# BSK3.net
KiCad netlist of a schematic drawn in EAGLE
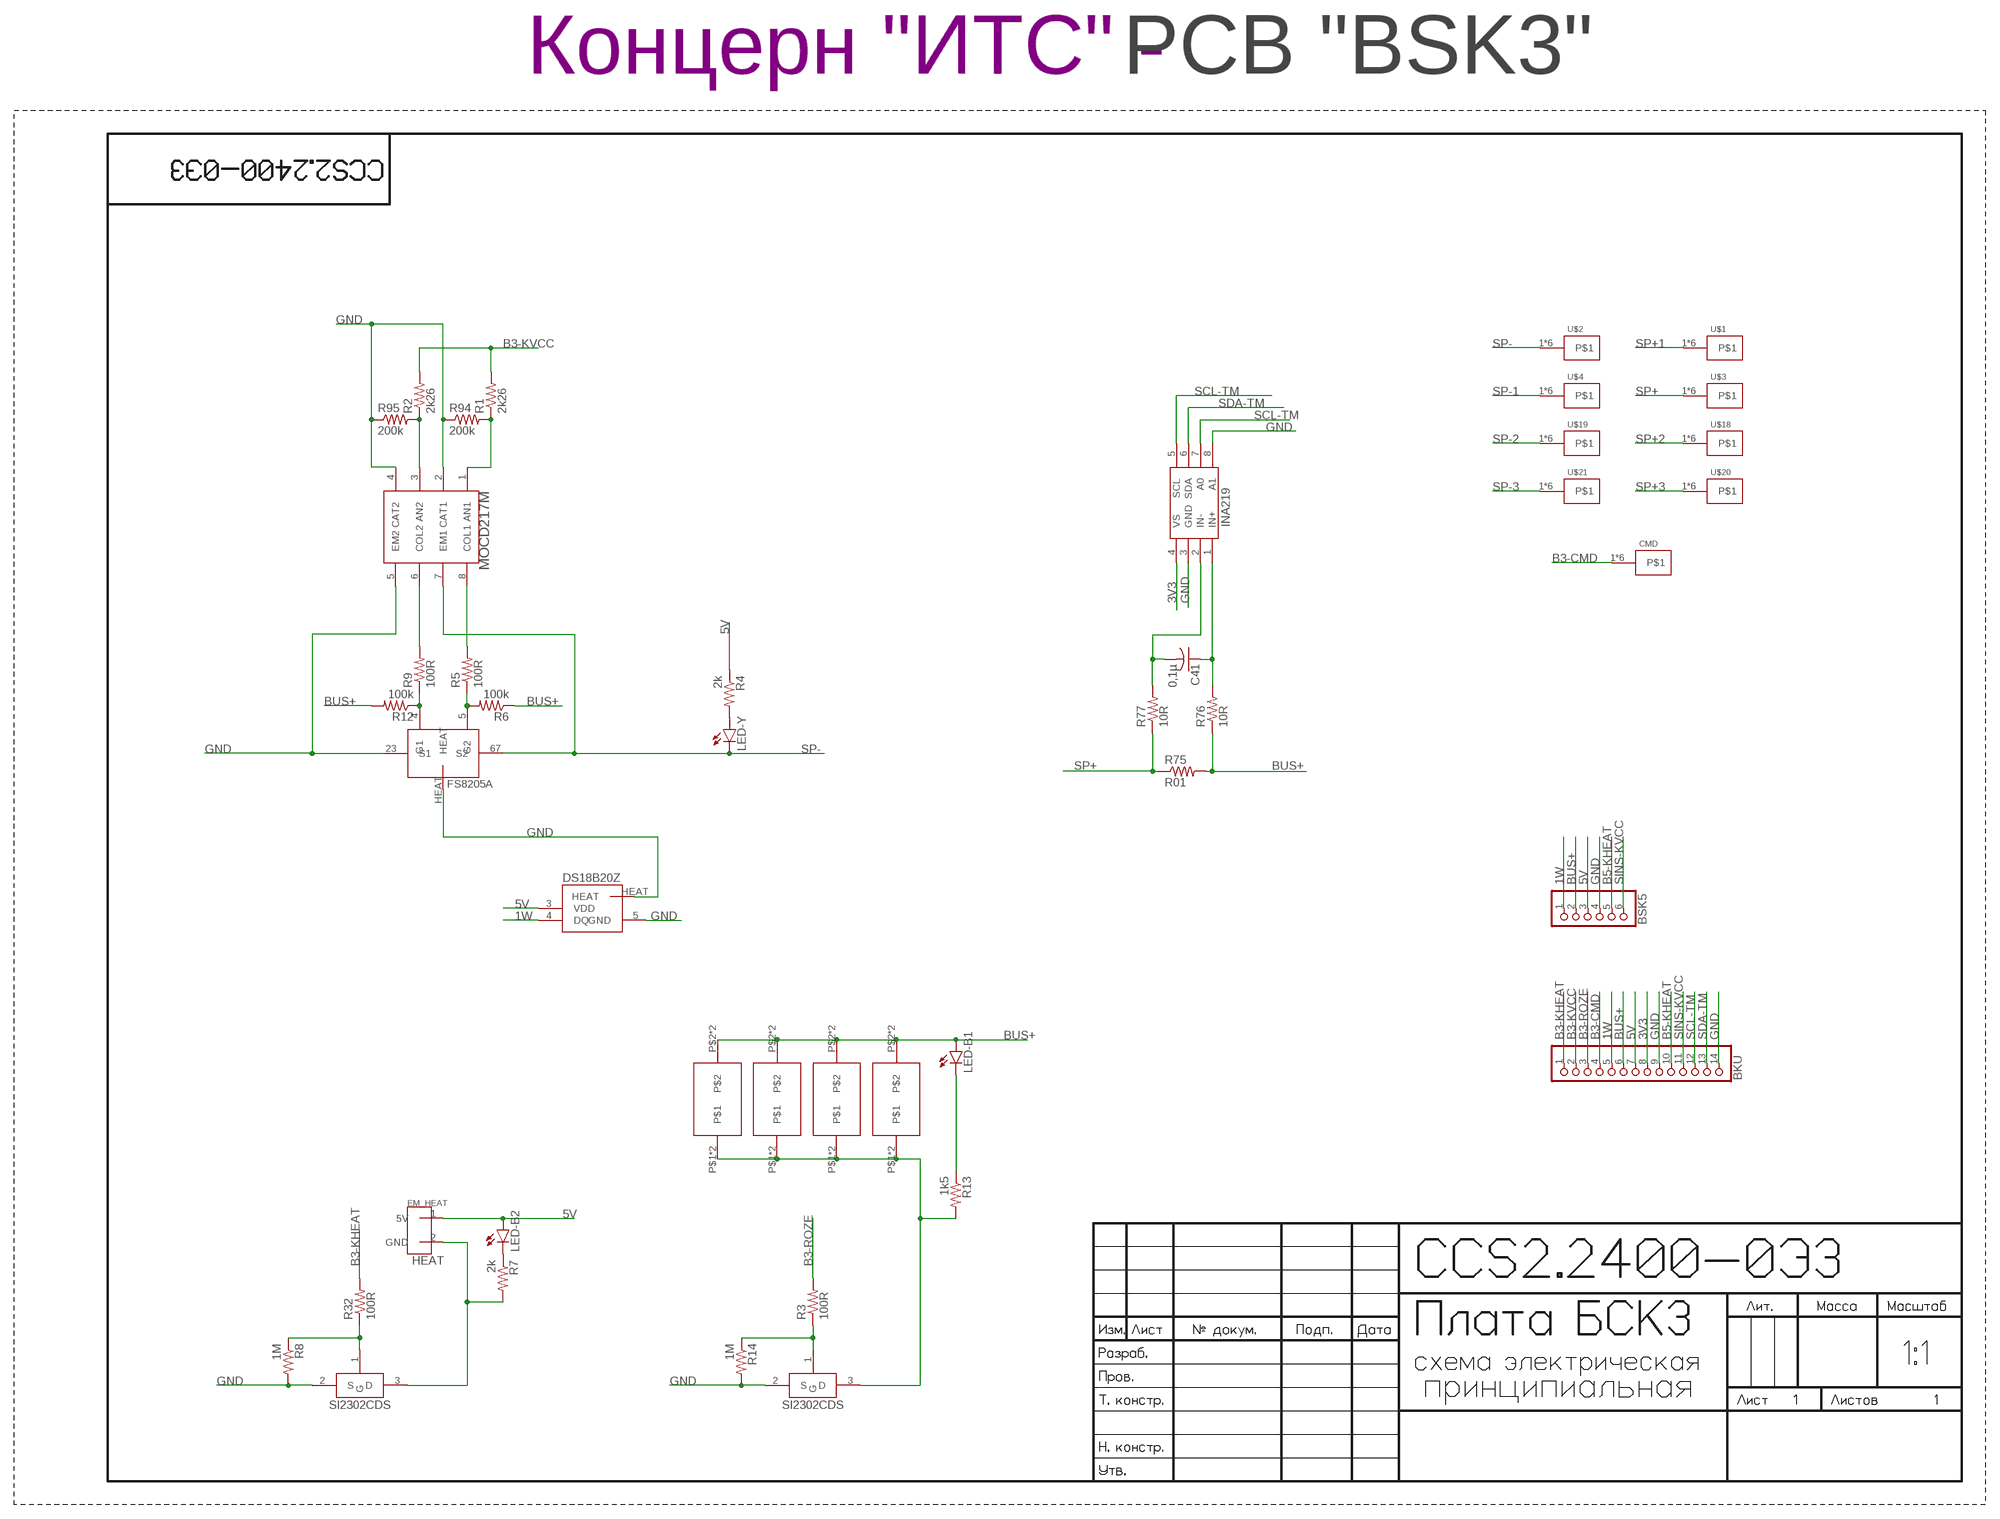
[diagram p0: schematic, sheet 1]

(export (version "E")
  (design (tool "Eeschema 10.0.6"))
  (components
    (comp (ref "BKU")
      (value "PINHD-1X14")
      (footprint "eagle-import:1X14")
      (libsource (lib "eagle-import") (part "PINHD-1X14"))
    )
    (comp (ref "BSK5")
      (value "PINHD-1X6")
      (footprint "eagle-import:1X06")
      (libsource (lib "eagle-import") (part "PINHD-1X6"))
    )
    (comp (ref "C41")
      (value "0,1µ")
      (footprint "eagle-import:C0603")
      (libsource (lib "eagle-import") (part "C-USC0603"))
    )
    (comp (ref "CMD")
      (value "KCONNECTQUAD")
      (footprint "eagle-import:KCONNECT_QUAD")
      (libsource (lib "eagle-import") (part "KCONNECTQUAD"))
    )
    (comp (ref "DS18B20Z")
      (value "DS18B20Z")
      (footprint "eagle-import:SOIC8+HEAT_S")
      (libsource (lib "eagle-import") (part "DS18B20Z"))
    )
    (comp (ref "INA")
      (value "INA219AID")
      (footprint "eagle-import:SOT23-8")
      (libsource (lib "eagle-import") (part "INA219AID"))
    )
    (comp (ref "LED-B1")
      (value "LEDCHIPLED_0603")
      (footprint "eagle-import:CHIPLED_0603")
      (libsource (lib "eagle-import") (part "LEDCHIPLED_0603"))
    )
    (comp (ref "LED-B2")
      (value "LEDCHIPLED_0603")
      (footprint "eagle-import:CHIPLED_0603")
      (libsource (lib "eagle-import") (part "LEDCHIPLED_0603"))
    )
    (comp (ref "LED-Y")
      (value "LAP4-BOTTOM")
      (footprint "eagle-import:P47F-BOTTOM")
      (libsource (lib "eagle-import") (part "P4-BOTTOMLA"))
    )
    (comp (ref "R1")
      (value "2k26")
      (footprint "eagle-import:R0603")
      (libsource (lib "eagle-import") (part "resistor_348_R-US_R0603"))
    )
    (comp (ref "R2")
      (value "2k26")
      (footprint "eagle-import:R0603")
      (libsource (lib "eagle-import") (part "resistor_348_R-US_R0603"))
    )
    (comp (ref "R3")
      (value "100R")
      (footprint "eagle-import:R0603")
      (libsource (lib "eagle-import") (part "resistor_R-US_R0603"))
    )
    (comp (ref "R4")
      (value "2k")
      (footprint "eagle-import:R0603")
      (libsource (lib "eagle-import") (part "resistor_348_R-US_R0603"))
    )
    (comp (ref "R5")
      (value "100R")
      (footprint "eagle-import:R0603")
      (libsource (lib "eagle-import") (part "resistor_348_R-US_R0603"))
    )
    (comp (ref "R6")
      (value "100k")
      (footprint "eagle-import:R0603")
      (libsource (lib "eagle-import") (part "resistor_348_R-US_R0603"))
    )
    (comp (ref "R7")
      (value "2k")
      (footprint "eagle-import:R0603")
      (libsource (lib "eagle-import") (part "resistor_348_R-US_R0603"))
    )
    (comp (ref "R8")
      (value "1M")
      (footprint "eagle-import:R0603")
      (libsource (lib "eagle-import") (part "resistor_348_R-US_R0603"))
    )
    (comp (ref "R9")
      (value "100R")
      (footprint "eagle-import:R0603")
      (libsource (lib "eagle-import") (part "resistor_348_R-US_R0603"))
    )
    (comp (ref "R12")
      (value "100k")
      (footprint "eagle-import:R0603")
      (libsource (lib "eagle-import") (part "resistor_348_R-US_R0603"))
    )
    (comp (ref "R13")
      (value "1k5")
      (footprint "eagle-import:R0603")
      (libsource (lib "eagle-import") (part "resistor_348_R-US_R0603"))
    )
    (comp (ref "R14")
      (value "1M")
      (footprint "eagle-import:R0603")
      (libsource (lib "eagle-import") (part "resistor_348_R-US_R0603"))
    )
    (comp (ref "R32")
      (value "100R")
      (footprint "eagle-import:R0603")
      (libsource (lib "eagle-import") (part "resistor_R-US_R0603"))
    )
    (comp (ref "R75")
      (value "R01")
      (footprint "eagle-import:R2512")
      (libsource (lib "eagle-import") (part "R-US_R2512"))
    )
    (comp (ref "R76")
      (value "10R")
      (footprint "eagle-import:R0603")
      (libsource (lib "eagle-import") (part "resistor_R-US_R0603"))
    )
    (comp (ref "R77")
      (value "10R")
      (footprint "eagle-import:R0603")
      (libsource (lib "eagle-import") (part "resistor_R-US_R0603"))
    )
    (comp (ref "R94")
      (value "200k")
      (footprint "eagle-import:R0603")
      (libsource (lib "eagle-import") (part "resistor_348_R-US_R0603"))
    )
    (comp (ref "R95")
      (value "200k")
      (footprint "eagle-import:R0603")
      (libsource (lib "eagle-import") (part "resistor_348_R-US_R0603"))
    )
    (comp (ref "U$1")
      (value "KCONNECT")
      (footprint "eagle-import:KCONNECT")
      (libsource (lib "eagle-import") (part "KCONNECT"))
    )
    (comp (ref "U$2")
      (value "KCONNECT")
      (footprint "eagle-import:KCONNECT")
      (libsource (lib "eagle-import") (part "KCONNECT"))
    )
    (comp (ref "U$3")
      (value "KCONNECT")
      (footprint "eagle-import:KCONNECT")
      (libsource (lib "eagle-import") (part "KCONNECT"))
    )
    (comp (ref "U$4")
      (value "KCONNECT")
      (footprint "eagle-import:KCONNECT")
      (libsource (lib "eagle-import") (part "KCONNECT"))
    )
    (comp (ref "U$5")
      (value "MOCD")
      (footprint "eagle-import:SOIC8")
      (libsource (lib "eagle-import") (part "MOCD217M"))
    )
    (comp (ref "U$6")
      (value "GRAFITGRAFIT4_2")
      (footprint "eagle-import:GRAFIT4_2")
      (libsource (lib "eagle-import") (part "GRAFITGRAFIT4_2"))
    )
    (comp (ref "U$7")
      (value "GRAFITGRAFIT4_2")
      (footprint "eagle-import:GRAFIT4_2")
      (libsource (lib "eagle-import") (part "GRAFITGRAFIT4_2"))
    )
    (comp (ref "U$8")
      (value "SI2302CDS")
      (footprint "eagle-import:SOT23-3")
      (libsource (lib "eagle-import") (part "SI2302CDS"))
    )
    (comp (ref "U$9")
      (value "PCB \"BSK3\"")
      (footprint "eagle-import:ITS-LOGO")
      (libsource (lib "eagle-import") (part "ITS-LOGOPCB-{dblquote}{dblquote}"))
    )
    (comp (ref "U$13")
      (value "SI2302CDS")
      (footprint "eagle-import:SOT23-3")
      (libsource (lib "eagle-import") (part "SI2302CDS"))
    )
    (comp (ref "U$14")
      (value "EM_HEAT")
      (footprint "eagle-import:EM_HEAT")
      (libsource (lib "eagle-import") (part "EM_HEAT"))
    )
    (comp (ref "U$15")
      (value "GRAFITGRAFIT4_2")
      (footprint "eagle-import:GRAFIT4_2")
      (libsource (lib "eagle-import") (part "GRAFITGRAFIT4_2"))
    )
    (comp (ref "U$16")
      (value "GRAFITGRAFIT4_2")
      (footprint "eagle-import:GRAFIT4_2")
      (libsource (lib "eagle-import") (part "GRAFITGRAFIT4_2"))
    )
    (comp (ref "U$18")
      (value "KCONNECT")
      (footprint "eagle-import:KCONNECT")
      (libsource (lib "eagle-import") (part "KCONNECT"))
    )
    (comp (ref "U$19")
      (value "KCONNECT")
      (footprint "eagle-import:KCONNECT")
      (libsource (lib "eagle-import") (part "KCONNECT"))
    )
    (comp (ref "U$20")
      (value "KCONNECT")
      (footprint "eagle-import:KCONNECT")
      (libsource (lib "eagle-import") (part "KCONNECT"))
    )
    (comp (ref "U$21")
      (value "KCONNECT")
      (footprint "eagle-import:KCONNECT")
      (libsource (lib "eagle-import") (part "KCONNECT"))
    )
    (comp (ref "U$26")
      (value "FS8205A+")
      (footprint "eagle-import:FS8205A+")
      (libsource (lib "eagle-import") (part "FS8205A+"))
    )
  )
  (nets
    (net (code "1") (name "/1W") (class "Default")
      (node (ref "BKU") (pin "5") (pinfunction "5_5") (pintype "passive"))
      (node (ref "BSK5") (pin "1") (pinfunction "1_1") (pintype "passive"))
      (node (ref "DS18B20Z") (pin "4") (pinfunction "DQ_4") (pintype "bidirectional"))
    )
    (net (code "2") (name "/3V3") (class "Default")
      (node (ref "BKU") (pin "8") (pinfunction "8_8") (pintype "passive"))
      (node (ref "INA") (pin "4") (pinfunction "VS_4") (pintype "bidirectional"))
    )
    (net (code "3") (name "/5V") (class "Default")
      (node (ref "BKU") (pin "7") (pinfunction "7_7") (pintype "passive"))
      (node (ref "BSK5") (pin "3") (pinfunction "3_3") (pintype "passive"))
      (node (ref "DS18B20Z") (pin "3") (pinfunction "VDD_3") (pintype "bidirectional"))
      (node (ref "LED-B2") (pin "A") (pinfunction "A_A") (pintype "passive"))
      (node (ref "R4") (pin "1") (pinfunction "1_1") (pintype "passive"))
      (node (ref "U$14") (pin "1") (pinfunction "5V_1") (pintype "bidirectional"))
    )
    (net (code "4") (name "/B3-CMD") (class "Default")
      (node (ref "BKU") (pin "4") (pinfunction "4_4") (pintype "passive"))
      (node (ref "CMD") (pin "1") (pinfunction "P$1_1") (pintype "bidirectional"))
      (node (ref "CMD") (pin "2") (pinfunction "P$1_2") (pintype "bidirectional"))
      (node (ref "CMD") (pin "3") (pinfunction "P$1_3") (pintype "bidirectional"))
      (node (ref "CMD") (pin "4") (pinfunction "P$1_4") (pintype "bidirectional"))
      (node (ref "CMD") (pin "P$1") (pinfunction "P$1_P$1") (pintype "bidirectional"))
      (node (ref "CMD") (pin "P$2") (pinfunction "P$1_P$2") (pintype "bidirectional"))
    )
    (net (code "5") (name "/B3-KHEAT") (class "Default")
      (node (ref "BKU") (pin "1") (pinfunction "1_1") (pintype "passive"))
      (node (ref "R32") (pin "2") (pinfunction "2_2") (pintype "passive"))
    )
    (net (code "6") (name "/B3-KVCC") (class "Default")
      (node (ref "BKU") (pin "2") (pinfunction "2_2") (pintype "passive"))
      (node (ref "R1") (pin "2") (pinfunction "2_2") (pintype "passive"))
      (node (ref "R2") (pin "2") (pinfunction "2_2") (pintype "passive"))
    )
    (net (code "7") (name "/B3-ROZE") (class "Default")
      (node (ref "BKU") (pin "3") (pinfunction "3_3") (pintype "passive"))
      (node (ref "R3") (pin "2") (pinfunction "2_2") (pintype "passive"))
    )
    (net (code "8") (name "/B5-KHEAT") (class "Default")
      (node (ref "BKU") (pin "10") (pinfunction "10_10") (pintype "passive"))
      (node (ref "BSK5") (pin "5") (pinfunction "5_5") (pintype "passive"))
    )
    (net (code "9") (name "/BUS+") (class "Default")
      (node (ref "BKU") (pin "6") (pinfunction "6_6") (pintype "passive"))
      (node (ref "BSK5") (pin "2") (pinfunction "2_2") (pintype "passive"))
      (node (ref "LED-B1") (pin "A") (pinfunction "A_A") (pintype "passive"))
      (node (ref "R12") (pin "2") (pinfunction "2_2") (pintype "passive"))
      (node (ref "R6") (pin "1") (pinfunction "1_1") (pintype "passive"))
      (node (ref "R75") (pin "2") (pinfunction "2_2") (pintype "passive"))
      (node (ref "R76") (pin "1") (pinfunction "1_1") (pintype "passive"))
      (node (ref "U$15") (pin "P$2") (pinfunction "P$2_P$2") (pintype "bidirectional"))
      (node (ref "U$15") (pin "P$5") (pinfunction "P$2_P$5") (pintype "bidirectional"))
      (node (ref "U$16") (pin "P$2") (pinfunction "P$2_P$2") (pintype "bidirectional"))
      (node (ref "U$16") (pin "P$5") (pinfunction "P$2_P$5") (pintype "bidirectional"))
      (node (ref "U$6") (pin "P$2") (pinfunction "P$2_P$2") (pintype "bidirectional"))
      (node (ref "U$6") (pin "P$5") (pinfunction "P$2_P$5") (pintype "bidirectional"))
      (node (ref "U$7") (pin "P$2") (pinfunction "P$2_P$2") (pintype "bidirectional"))
      (node (ref "U$7") (pin "P$5") (pinfunction "P$2_P$5") (pintype "bidirectional"))
    )
    (net (code "10") (name "/GND") (class "Default")
      (node (ref "BKU") (pin "14") (pinfunction "14_14") (pintype "passive"))
      (node (ref "BKU") (pin "9") (pinfunction "9_9") (pintype "passive"))
      (node (ref "BSK5") (pin "4") (pinfunction "4_4") (pintype "passive"))
      (node (ref "DS18B20Z") (pin "5") (pinfunction "GND_5") (pintype "bidirectional"))
      (node (ref "DS18B20Z") (pin "HEAT") (pinfunction "HEAT_HEAT") (pintype "bidirectional"))
      (node (ref "INA") (pin "3") (pinfunction "GND_3") (pintype "bidirectional"))
      (node (ref "INA") (pin "8") (pinfunction "A1_8") (pintype "bidirectional"))
      (node (ref "R14") (pin "2") (pinfunction "2_2") (pintype "passive"))
      (node (ref "R8") (pin "2") (pinfunction "2_2") (pintype "passive"))
      (node (ref "R94") (pin "1") (pinfunction "1_1") (pintype "passive"))
      (node (ref "R95") (pin "1") (pinfunction "1_1") (pintype "passive"))
      (node (ref "U$13") (pin "2") (pinfunction "S_2") (pintype "bidirectional"))
      (node (ref "U$26") (pin "23") (pinfunction "S1_23") (pintype "bidirectional"))
      (node (ref "U$26") (pin "HEAT") (pinfunction "HEAT_HEAT") (pintype "bidirectional"))
      (node (ref "U$5") (pin "2") (pinfunction "CAT1_2") (pintype "bidirectional"))
      (node (ref "U$5") (pin "4") (pinfunction "CAT2_4") (pintype "bidirectional"))
      (node (ref "U$5") (pin "5") (pinfunction "EM2_5") (pintype "bidirectional"))
      (node (ref "U$8") (pin "2") (pinfunction "S_2") (pintype "bidirectional"))
    )
    (net (code "11") (name "/SCL-TM") (class "Default")
      (node (ref "BKU") (pin "12") (pinfunction "12_12") (pintype "passive"))
      (node (ref "INA") (pin "5") (pinfunction "SCL_5") (pintype "bidirectional"))
      (node (ref "INA") (pin "7") (pinfunction "A0_7") (pintype "bidirectional"))
    )
    (net (code "12") (name "/SDA-TM") (class "Default")
      (node (ref "BKU") (pin "13") (pinfunction "13_13") (pintype "passive"))
      (node (ref "INA") (pin "6") (pinfunction "SDA_6") (pintype "bidirectional"))
    )
    (net (code "13") (name "/SINS-KVCC") (class "Default")
      (node (ref "BKU") (pin "11") (pinfunction "11_11") (pintype "passive"))
      (node (ref "BSK5") (pin "6") (pinfunction "6_6") (pintype "passive"))
    )
    (net (code "14") (name "/SP+") (class "Default")
      (node (ref "R75") (pin "1") (pinfunction "1_1") (pintype "passive"))
      (node (ref "R77") (pin "1") (pinfunction "1_1") (pintype "passive"))
      (node (ref "U$3") (pin "1") (pinfunction "P$1_1") (pintype "bidirectional"))
      (node (ref "U$3") (pin "2") (pinfunction "P$1_2") (pintype "bidirectional"))
      (node (ref "U$3") (pin "3") (pinfunction "P$1_3") (pintype "bidirectional"))
      (node (ref "U$3") (pin "4") (pinfunction "P$1_4") (pintype "bidirectional"))
      (node (ref "U$3") (pin "P$1") (pinfunction "P$1_P$1") (pintype "bidirectional"))
      (node (ref "U$3") (pin "P$2") (pinfunction "P$1_P$2") (pintype "bidirectional"))
    )
    (net (code "15") (name "/SP+1") (class "Default")
      (node (ref "U$1") (pin "1") (pinfunction "P$1_1") (pintype "bidirectional"))
      (node (ref "U$1") (pin "2") (pinfunction "P$1_2") (pintype "bidirectional"))
      (node (ref "U$1") (pin "3") (pinfunction "P$1_3") (pintype "bidirectional"))
      (node (ref "U$1") (pin "4") (pinfunction "P$1_4") (pintype "bidirectional"))
      (node (ref "U$1") (pin "P$1") (pinfunction "P$1_P$1") (pintype "bidirectional"))
      (node (ref "U$1") (pin "P$2") (pinfunction "P$1_P$2") (pintype "bidirectional"))
    )
    (net (code "16") (name "/SP+2") (class "Default")
      (node (ref "U$18") (pin "1") (pinfunction "P$1_1") (pintype "bidirectional"))
      (node (ref "U$18") (pin "2") (pinfunction "P$1_2") (pintype "bidirectional"))
      (node (ref "U$18") (pin "3") (pinfunction "P$1_3") (pintype "bidirectional"))
      (node (ref "U$18") (pin "4") (pinfunction "P$1_4") (pintype "bidirectional"))
      (node (ref "U$18") (pin "P$1") (pinfunction "P$1_P$1") (pintype "bidirectional"))
      (node (ref "U$18") (pin "P$2") (pinfunction "P$1_P$2") (pintype "bidirectional"))
    )
    (net (code "17") (name "/SP+3") (class "Default")
      (node (ref "U$20") (pin "1") (pinfunction "P$1_1") (pintype "bidirectional"))
      (node (ref "U$20") (pin "2") (pinfunction "P$1_2") (pintype "bidirectional"))
      (node (ref "U$20") (pin "3") (pinfunction "P$1_3") (pintype "bidirectional"))
      (node (ref "U$20") (pin "4") (pinfunction "P$1_4") (pintype "bidirectional"))
      (node (ref "U$20") (pin "P$1") (pinfunction "P$1_P$1") (pintype "bidirectional"))
      (node (ref "U$20") (pin "P$2") (pinfunction "P$1_P$2") (pintype "bidirectional"))
    )
    (net (code "18") (name "/SP-") (class "Default")
      (node (ref "LED-Y") (pin "C") (pinfunction "C_C") (pintype "passive"))
      (node (ref "U$2") (pin "1") (pinfunction "P$1_1") (pintype "bidirectional"))
      (node (ref "U$2") (pin "2") (pinfunction "P$1_2") (pintype "bidirectional"))
      (node (ref "U$2") (pin "3") (pinfunction "P$1_3") (pintype "bidirectional"))
      (node (ref "U$2") (pin "4") (pinfunction "P$1_4") (pintype "bidirectional"))
      (node (ref "U$2") (pin "P$1") (pinfunction "P$1_P$1") (pintype "bidirectional"))
      (node (ref "U$2") (pin "P$2") (pinfunction "P$1_P$2") (pintype "bidirectional"))
      (node (ref "U$26") (pin "67") (pinfunction "S2_67") (pintype "bidirectional"))
      (node (ref "U$5") (pin "7") (pinfunction "EM1_7") (pintype "bidirectional"))
    )
    (net (code "19") (name "/SP-1") (class "Default")
      (node (ref "U$4") (pin "1") (pinfunction "P$1_1") (pintype "bidirectional"))
      (node (ref "U$4") (pin "2") (pinfunction "P$1_2") (pintype "bidirectional"))
      (node (ref "U$4") (pin "3") (pinfunction "P$1_3") (pintype "bidirectional"))
      (node (ref "U$4") (pin "4") (pinfunction "P$1_4") (pintype "bidirectional"))
      (node (ref "U$4") (pin "P$1") (pinfunction "P$1_P$1") (pintype "bidirectional"))
      (node (ref "U$4") (pin "P$2") (pinfunction "P$1_P$2") (pintype "bidirectional"))
    )
    (net (code "20") (name "/SP-2") (class "Default")
      (node (ref "U$19") (pin "1") (pinfunction "P$1_1") (pintype "bidirectional"))
      (node (ref "U$19") (pin "2") (pinfunction "P$1_2") (pintype "bidirectional"))
      (node (ref "U$19") (pin "3") (pinfunction "P$1_3") (pintype "bidirectional"))
      (node (ref "U$19") (pin "4") (pinfunction "P$1_4") (pintype "bidirectional"))
      (node (ref "U$19") (pin "P$1") (pinfunction "P$1_P$1") (pintype "bidirectional"))
      (node (ref "U$19") (pin "P$2") (pinfunction "P$1_P$2") (pintype "bidirectional"))
    )
    (net (code "21") (name "/SP-3") (class "Default")
      (node (ref "U$21") (pin "1") (pinfunction "P$1_1") (pintype "bidirectional"))
      (node (ref "U$21") (pin "2") (pinfunction "P$1_2") (pintype "bidirectional"))
      (node (ref "U$21") (pin "3") (pinfunction "P$1_3") (pintype "bidirectional"))
      (node (ref "U$21") (pin "4") (pinfunction "P$1_4") (pintype "bidirectional"))
      (node (ref "U$21") (pin "P$1") (pinfunction "P$1_P$1") (pintype "bidirectional"))
      (node (ref "U$21") (pin "P$2") (pinfunction "P$1_P$2") (pintype "bidirectional"))
    )
    (net (code "22") (name "Net-(INA-IN+)") (class "Default")
      (node (ref "C41") (pin "1") (pinfunction "1_1") (pintype "passive"))
      (node (ref "INA") (pin "1") (pinfunction "IN+_1") (pintype "bidirectional"))
      (node (ref "R76") (pin "2") (pinfunction "2_2") (pintype "passive"))
    )
    (net (code "23") (name "Net-(INA-IN-)") (class "Default")
      (node (ref "C41") (pin "2") (pinfunction "2_2") (pintype "passive"))
      (node (ref "INA") (pin "2") (pinfunction "IN-_2") (pintype "bidirectional"))
      (node (ref "R77") (pin "2") (pinfunction "2_2") (pintype "passive"))
    )
    (net (code "24") (name "Net-(LED-B1-PadC)") (class "Default")
      (node (ref "LED-B1") (pin "C") (pinfunction "C_C") (pintype "passive"))
      (node (ref "R13") (pin "1") (pinfunction "1_1") (pintype "passive"))
    )
    (net (code "25") (name "Net-(LED-B2-PadC)") (class "Default")
      (node (ref "LED-B2") (pin "C") (pinfunction "C_C") (pintype "passive"))
      (node (ref "R7") (pin "1") (pinfunction "1_1") (pintype "passive"))
    )
    (net (code "26") (name "Net-(LED-Y-PadA)") (class "Default")
      (node (ref "LED-Y") (pin "A") (pinfunction "A_A") (pintype "passive"))
      (node (ref "R4") (pin "2") (pinfunction "2_2") (pintype "passive"))
    )
    (net (code "27") (name "Net-(U$5-AN1)") (class "Default")
      (node (ref "R1") (pin "1") (pinfunction "1_1") (pintype "passive"))
      (node (ref "R94") (pin "2") (pinfunction "2_2") (pintype "passive"))
      (node (ref "U$5") (pin "1") (pinfunction "AN1_1") (pintype "bidirectional"))
    )
    (net (code "28") (name "Net-(U$5-AN2)") (class "Default")
      (node (ref "R2") (pin "1") (pinfunction "1_1") (pintype "passive"))
      (node (ref "R95") (pin "2") (pinfunction "2_2") (pintype "passive"))
      (node (ref "U$5") (pin "3") (pinfunction "AN2_3") (pintype "bidirectional"))
    )
    (net (code "29") (name "Net-(U$5-COL1)") (class "Default")
      (node (ref "R5") (pin "2") (pinfunction "2_2") (pintype "passive"))
      (node (ref "U$5") (pin "8") (pinfunction "COL1_8") (pintype "bidirectional"))
    )
    (net (code "30") (name "Net-(U$5-COL2)") (class "Default")
      (node (ref "R9") (pin "2") (pinfunction "2_2") (pintype "passive"))
      (node (ref "U$5") (pin "6") (pinfunction "COL2_6") (pintype "bidirectional"))
    )
    (net (code "31") (name "Net-(U$8-G)") (class "Default")
      (node (ref "R32") (pin "1") (pinfunction "1_1") (pintype "passive"))
      (node (ref "R8") (pin "1") (pinfunction "1_1") (pintype "passive"))
      (node (ref "U$8") (pin "1") (pinfunction "G_1") (pintype "bidirectional"))
    )
    (net (code "32") (name "Net-(U$13-D)") (class "Default")
      (node (ref "R13") (pin "2") (pinfunction "2_2") (pintype "passive"))
      (node (ref "U$13") (pin "3") (pinfunction "D_3") (pintype "bidirectional"))
      (node (ref "U$15") (pin "P$1") (pinfunction "P$1_P$1") (pintype "bidirectional"))
      (node (ref "U$15") (pin "P$4") (pinfunction "P$1_P$4") (pintype "bidirectional"))
      (node (ref "U$16") (pin "P$1") (pinfunction "P$1_P$1") (pintype "bidirectional"))
      (node (ref "U$16") (pin "P$4") (pinfunction "P$1_P$4") (pintype "bidirectional"))
      (node (ref "U$6") (pin "P$1") (pinfunction "P$1_P$1") (pintype "bidirectional"))
      (node (ref "U$6") (pin "P$4") (pinfunction "P$1_P$4") (pintype "bidirectional"))
      (node (ref "U$7") (pin "P$1") (pinfunction "P$1_P$1") (pintype "bidirectional"))
      (node (ref "U$7") (pin "P$4") (pinfunction "P$1_P$4") (pintype "bidirectional"))
    )
    (net (code "33") (name "Net-(U$13-G)") (class "Default")
      (node (ref "R14") (pin "1") (pinfunction "1_1") (pintype "passive"))
      (node (ref "R3") (pin "1") (pinfunction "1_1") (pintype "passive"))
      (node (ref "U$13") (pin "1") (pinfunction "G_1") (pintype "bidirectional"))
    )
    (net (code "34") (name "Net-(U$14-GND)") (class "Default")
      (node (ref "R7") (pin "2") (pinfunction "2_2") (pintype "passive"))
      (node (ref "U$14") (pin "2") (pinfunction "GND_2") (pintype "bidirectional"))
      (node (ref "U$8") (pin "3") (pinfunction "D_3") (pintype "bidirectional"))
    )
    (net (code "35") (name "Net-(U$26-G1)") (class "Default")
      (node (ref "R12") (pin "1") (pinfunction "1_1") (pintype "passive"))
      (node (ref "R9") (pin "1") (pinfunction "1_1") (pintype "passive"))
      (node (ref "U$26") (pin "4") (pinfunction "G1_4") (pintype "bidirectional"))
    )
    (net (code "36") (name "Net-(U$26-G2)") (class "Default")
      (node (ref "R5") (pin "1") (pinfunction "1_1") (pintype "passive"))
      (node (ref "R6") (pin "2") (pinfunction "2_2") (pintype "passive"))
      (node (ref "U$26") (pin "5") (pinfunction "G2_5") (pintype "bidirectional"))
    )
  )
)
